# sensorCR123.net
KiCad netlist of a schematic drawn in EAGLE
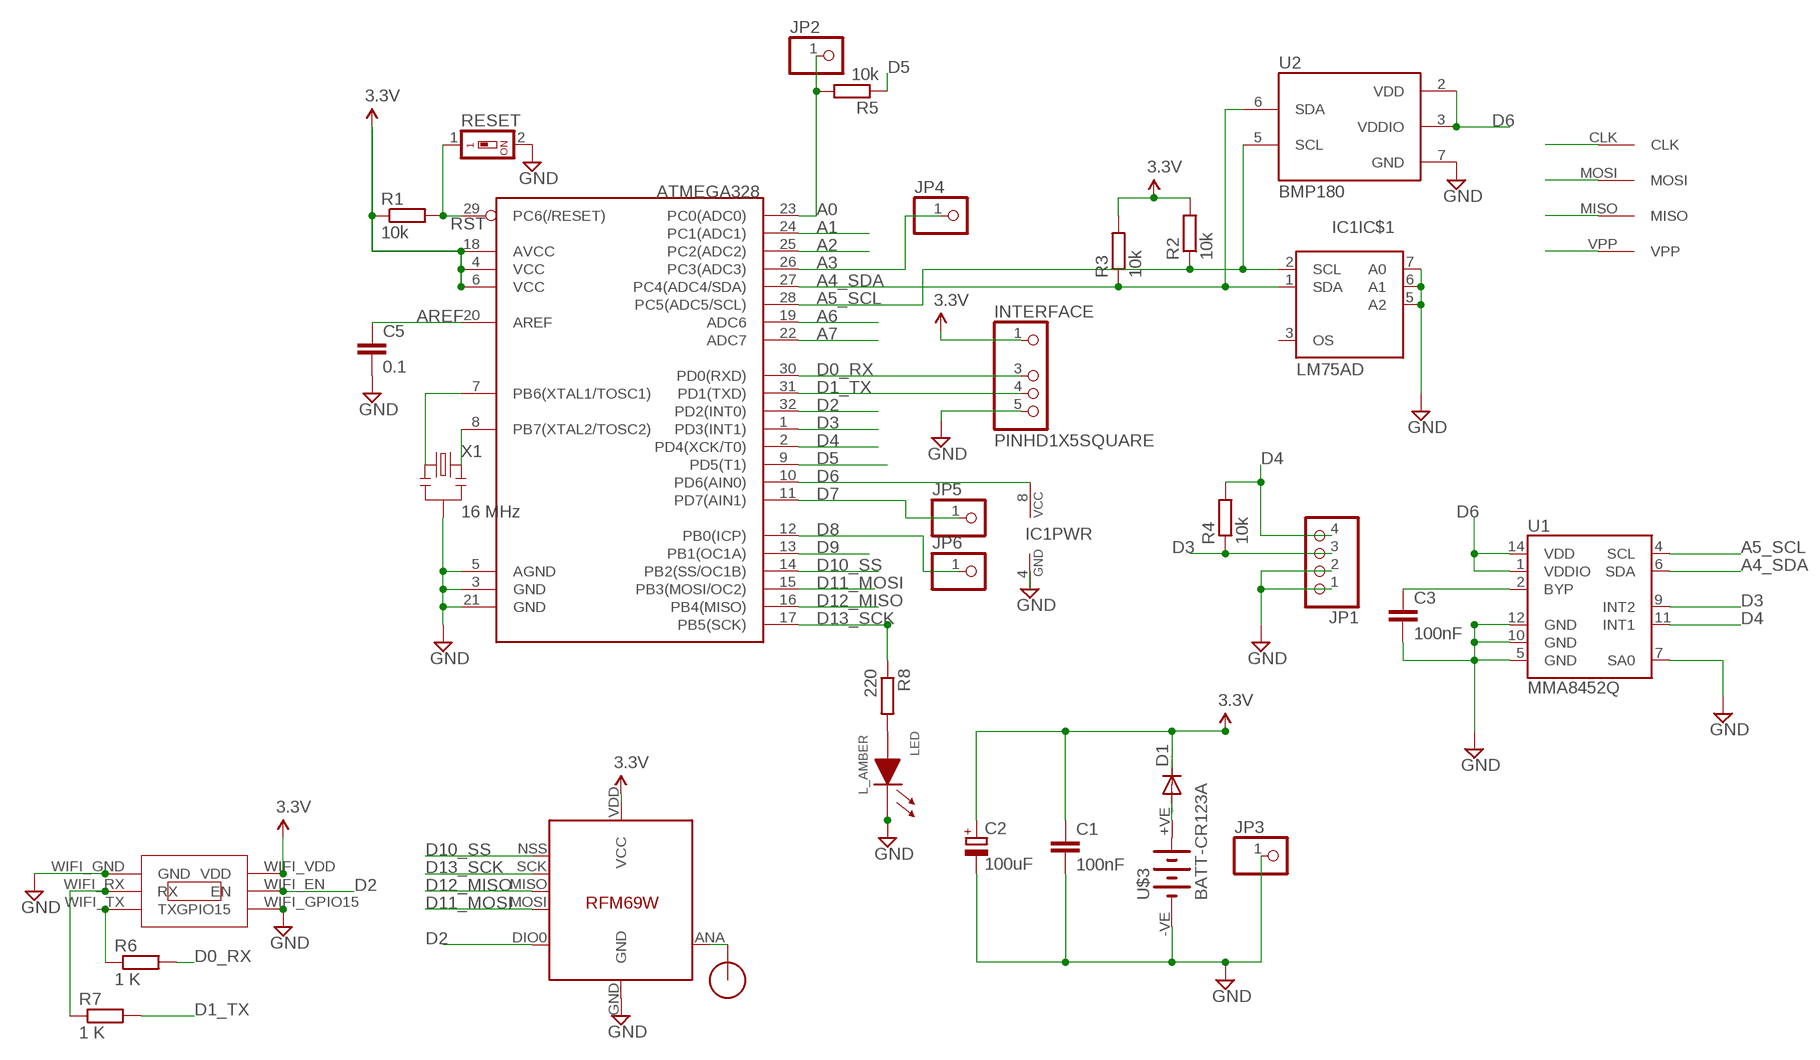
[diagram p0: schematic, sheet 1]

(export (version "E")
  (design (tool "Eeschema 10.0.6"))
  (components
    (comp (ref "ATMEGA328")
      (value "ATMega-328")
      (footprint "eagle-import:TQFP32-08")
      (libsource (lib "eagle-import") (part "ATMEGA168/328TQFP32"))
    )
    (comp (ref "C1")
      (value "100nF")
      (footprint "eagle-import:C2012")
      (libsource (lib "eagle-import") (part "C-EUC2012"))
    )
    (comp (ref "C2")
      (value "100uF")
      (footprint "eagle-import:SMC_B")
      (libsource (lib "eagle-import") (part "CPOL-EUSMCB"))
    )
    (comp (ref "C3")
      (value "100nF")
      (footprint "eagle-import:C2012")
      (libsource (lib "eagle-import") (part "C-EUC2012"))
    )
    (comp (ref "C5")
      (value "0.1")
      (footprint "eagle-import:C2012")
      (libsource (lib "eagle-import") (part "C-EUC2012"))
    )
    (comp (ref "D1")
      (value "DIODE-DO214BA")
      (footprint "eagle-import:DO214BA")
      (libsource (lib "eagle-import") (part "DIODE-DO214BA"))
    )
    (comp (ref "IC1")
      (value "LM75AD")
      (footprint "eagle-import:SO08")
      (libsource (lib "eagle-import") (part "LM75AD"))
    )
    (comp (ref "INTERFACE")
      (value "PINHD1X5SQUARE")
      (footprint "eagle-import:PINHD1X05-SQUARE")
      (libsource (lib "eagle-import") (part "PINHD1X5SQUARE"))
    )
    (comp (ref "JP1")
      (value "PINHD-1X04_2.54-S")
      (footprint "eagle-import:1X04-S")
      (libsource (lib "eagle-import") (part "PINHD-1X04_2.54-S"))
    )
    (comp (ref "JP2")
      (value "PINHD-1X01_2.54")
      (footprint "eagle-import:1X01")
      (libsource (lib "eagle-import") (part "PINHD-1X01_2.54"))
    )
    (comp (ref "JP3")
      (value "PINHD-1X01_2.54")
      (footprint "eagle-import:1X01")
      (libsource (lib "eagle-import") (part "PINHD-1X01_2.54"))
    )
    (comp (ref "JP4")
      (value "PINHD-1X01_2.54")
      (footprint "eagle-import:1X01")
      (libsource (lib "eagle-import") (part "PINHD-1X01_2.54"))
    )
    (comp (ref "JP5")
      (value "PINHD-1X01_2.54")
      (footprint "eagle-import:1X01")
      (libsource (lib "eagle-import") (part "PINHD-1X01_2.54"))
    )
    (comp (ref "JP6")
      (value "PINHD-1X01_2.54")
      (footprint "eagle-import:1X01")
      (libsource (lib "eagle-import") (part "PINHD-1X01_2.54"))
    )
    (comp (ref "LED")
      (value "L_AMBER")
      (footprint "eagle-import:LED0805")
      (libsource (lib "eagle-import") (part "LED0805"))
    )
    (comp (ref "R1")
      (value "10k")
      (footprint "eagle-import:R2012")
      (libsource (lib "eagle-import") (part "R-EU_R2012"))
    )
    (comp (ref "R2")
      (value "10k")
      (footprint "eagle-import:R2012")
      (libsource (lib "eagle-import") (part "R-EU_R2012"))
    )
    (comp (ref "R3")
      (value "10k")
      (footprint "eagle-import:R2012")
      (libsource (lib "eagle-import") (part "R-EU_R2012"))
    )
    (comp (ref "R4")
      (value "10k")
      (footprint "eagle-import:R2012")
      (libsource (lib "eagle-import") (part "R-EU_R2012"))
    )
    (comp (ref "R5")
      (value "10k")
      (footprint "eagle-import:R2012")
      (libsource (lib "eagle-import") (part "R-EU_R2012"))
    )
    (comp (ref "R6")
      (value "1 K")
      (footprint "eagle-import:M2012")
      (libsource (lib "eagle-import") (part "R-EU_M2012"))
    )
    (comp (ref "R7")
      (value "1 K")
      (footprint "eagle-import:M2012")
      (libsource (lib "eagle-import") (part "R-EU_M2012"))
    )
    (comp (ref "R8")
      (value "220")
      (footprint "eagle-import:M2012")
      (libsource (lib "eagle-import") (part "R-EU_M2012"))
    )
    (comp (ref "RESET")
      (value "SWS001")
      (footprint "eagle-import:SMS-001")
      (libsource (lib "eagle-import") (part "SWS001"))
    )
    (comp (ref "U$1")
      (value "RFM12B_ANTENNA")
      (footprint "eagle-import:RFM12B-ANTENNA")
      (libsource (lib "eagle-import") (part "RFM12B_ANTENNA"))
    )
    (comp (ref "U$2")
      (value "AVRHEADERDIP")
      (footprint "eagle-import:AVRHEADER")
      (libsource (lib "eagle-import") (part "AVRHEADERDIP"))
    )
    (comp (ref "U$3")
      (value "BATT-CR123A")
      (footprint "eagle-import:KEYSTONE-2_3A")
      (libsource (lib "eagle-import") (part "BATT-CR123A"))
    )
    (comp (ref "U$4")
      (value "RFM69W")
      (footprint "eagle-import:RFM69W")
      (libsource (lib "eagle-import") (part "RFM69W"))
    )
    (comp (ref "U$5")
      (value "ESP03")
      (footprint "eagle-import:ESP03")
      (libsource (lib "eagle-import") (part "ESP03"))
    )
    (comp (ref "U1")
      (value "MMA8452Q")
      (footprint "eagle-import:QFN-16_0.5MM")
      (libsource (lib "eagle-import") (part "MMA8452Q"))
    )
    (comp (ref "U2")
      (value "BMP180")
      (footprint "eagle-import:BMP180")
      (libsource (lib "eagle-import") (part "BMP180"))
    )
    (comp (ref "X1")
      (value "16 MHz")
      (footprint "eagle-import:RESONATOR-SMD")
      (libsource (lib "eagle-import") (part "RESONATORSMD"))
    )
  )
  (nets
    (net (code "1") (name "/A0") (class "Default")
      (node (ref "ATMEGA328") (pin "23") (pinfunction "PC0(ADC0)_23") (pintype "bidirectional"))
      (node (ref "JP2") (pin "1") (pinfunction "1_1") (pintype "passive"))
      (node (ref "R5") (pin "2") (pinfunction "2_2") (pintype "passive"))
    )
    (net (code "2") (name "/A1") (class "Default")
      (node (ref "ATMEGA328") (pin "24") (pinfunction "PC1(ADC1)_24") (pintype "bidirectional"))
    )
    (net (code "3") (name "/A2") (class "Default")
      (node (ref "ATMEGA328") (pin "25") (pinfunction "PC2(ADC2)_25") (pintype "bidirectional"))
    )
    (net (code "4") (name "/A3") (class "Default")
      (node (ref "ATMEGA328") (pin "26") (pinfunction "PC3(ADC3)_26") (pintype "bidirectional"))
      (node (ref "JP4") (pin "1") (pinfunction "1_1") (pintype "passive"))
    )
    (net (code "5") (name "/A4_SDA") (class "Default")
      (node (ref "ATMEGA328") (pin "27") (pinfunction "PC4(ADC4/SDA)_27") (pintype "bidirectional"))
      (node (ref "IC1") (pin "1") (pinfunction "SDA_1") (pintype "bidirectional"))
      (node (ref "R3") (pin "1") (pinfunction "1_1") (pintype "passive"))
      (node (ref "U1") (pin "6") (pinfunction "SDA_6") (pintype "bidirectional"))
      (node (ref "U2") (pin "6") (pinfunction "SDA_6") (pintype "bidirectional"))
    )
    (net (code "6") (name "/A5_SCL") (class "Default")
      (node (ref "ATMEGA328") (pin "28") (pinfunction "PC5(ADC5/SCL)_28") (pintype "bidirectional"))
      (node (ref "IC1") (pin "2") (pinfunction "SCL_2") (pintype "input"))
      (node (ref "R2") (pin "1") (pinfunction "1_1") (pintype "passive"))
      (node (ref "U1") (pin "4") (pinfunction "SCL_4") (pintype "bidirectional"))
      (node (ref "U2") (pin "5") (pinfunction "SCL_5") (pintype "input"))
    )
    (net (code "7") (name "/A6") (class "Default")
      (node (ref "ATMEGA328") (pin "19") (pinfunction "ADC6_19") (pintype "bidirectional"))
    )
    (net (code "8") (name "/A7") (class "Default")
      (node (ref "ATMEGA328") (pin "22") (pinfunction "ADC7_22") (pintype "bidirectional"))
    )
    (net (code "9") (name "/AREF") (class "Default")
      (node (ref "ATMEGA328") (pin "20") (pinfunction "AREF_20") (pintype "bidirectional"))
      (node (ref "C5") (pin "1") (pinfunction "1_1") (pintype "passive"))
    )
    (net (code "10") (name "/D0_RX") (class "Default")
      (node (ref "ATMEGA328") (pin "30") (pinfunction "PD0(RXD)_30") (pintype "bidirectional"))
      (node (ref "INTERFACE") (pin "3") (pinfunction "3_3") (pintype "passive"))
      (node (ref "R6") (pin "2") (pinfunction "2_2") (pintype "passive"))
    )
    (net (code "11") (name "/D1_TX") (class "Default")
      (node (ref "ATMEGA328") (pin "31") (pinfunction "PD1(TXD)_31") (pintype "bidirectional"))
      (node (ref "INTERFACE") (pin "4") (pinfunction "4_4") (pintype "passive"))
      (node (ref "R7") (pin "2") (pinfunction "2_2") (pintype "passive"))
    )
    (net (code "12") (name "/D2") (class "Default")
      (node (ref "ATMEGA328") (pin "32") (pinfunction "PD2(INT0)_32") (pintype "bidirectional"))
      (node (ref "U$4") (pin "DIO0") (pinfunction "DIO0_DIO0") (pintype "open_collector"))
      (node (ref "U$5") (pin "WIFI_EN") (pinfunction "EN_WIFI_EN") (pintype "input"))
    )
    (net (code "13") (name "/D3") (class "Default")
      (node (ref "ATMEGA328") (pin "1") (pinfunction "PD3(INT1)_1") (pintype "bidirectional"))
      (node (ref "JP1") (pin "3") (pinfunction "3_3") (pintype "passive"))
      (node (ref "R4") (pin "1") (pinfunction "1_1") (pintype "passive"))
      (node (ref "U1") (pin "9") (pinfunction "INT2_9") (pintype "bidirectional"))
    )
    (net (code "14") (name "/D4") (class "Default")
      (node (ref "ATMEGA328") (pin "2") (pinfunction "PD4(XCK/T0)_2") (pintype "bidirectional"))
      (node (ref "JP1") (pin "4") (pinfunction "4_4") (pintype "passive"))
      (node (ref "R4") (pin "2") (pinfunction "2_2") (pintype "passive"))
      (node (ref "U1") (pin "11") (pinfunction "INT1_11") (pintype "bidirectional"))
    )
    (net (code "15") (name "/D5") (class "Default")
      (node (ref "ATMEGA328") (pin "9") (pinfunction "PD5(T1)_9") (pintype "bidirectional"))
      (node (ref "R5") (pin "1") (pinfunction "1_1") (pintype "passive"))
    )
    (net (code "16") (name "/D6") (class "Default")
      (node (ref "ATMEGA328") (pin "10") (pinfunction "PD6(AIN0)_10") (pintype "bidirectional"))
      (node (ref "IC1") (pin "8") (pinfunction "VCC_8") (pintype "power_in"))
      (node (ref "U1") (pin "1") (pinfunction "VDDIO_1") (pintype "bidirectional"))
      (node (ref "U1") (pin "14") (pinfunction "VDD_14") (pintype "bidirectional"))
      (node (ref "U2") (pin "2") (pinfunction "VDD_2") (pintype "power_in"))
      (node (ref "U2") (pin "3") (pinfunction "VDDIO_3") (pintype "power_in"))
    )
    (net (code "17") (name "/D7") (class "Default")
      (node (ref "ATMEGA328") (pin "11") (pinfunction "PD7(AIN1)_11") (pintype "bidirectional"))
      (node (ref "JP5") (pin "1") (pinfunction "1_1") (pintype "passive"))
    )
    (net (code "18") (name "/D8") (class "Default")
      (node (ref "ATMEGA328") (pin "12") (pinfunction "PB0(ICP)_12") (pintype "bidirectional"))
      (node (ref "JP6") (pin "1") (pinfunction "1_1") (pintype "passive"))
    )
    (net (code "19") (name "/D9") (class "Default")
      (node (ref "ATMEGA328") (pin "13") (pinfunction "PB1(OC1A)_13") (pintype "bidirectional"))
    )
    (net (code "20") (name "/D10_SS") (class "Default")
      (node (ref "ATMEGA328") (pin "14") (pinfunction "PB2(SS/OC1B)_14") (pintype "bidirectional"))
      (node (ref "U$4") (pin "NSS") (pinfunction "SEL_NSS") (pintype "input"))
    )
    (net (code "21") (name "/D11_MOSI") (class "Default")
      (node (ref "ATMEGA328") (pin "15") (pinfunction "PB3(MOSI/OC2)_15") (pintype "bidirectional"))
      (node (ref "U$2") (pin "MOSI") (pinfunction "MOSI_MOSI") (pintype "bidirectional"))
      (node (ref "U$4") (pin "MOSI") (pinfunction "MOSI_MOSI") (pintype "output"))
    )
    (net (code "22") (name "/D12_MISO") (class "Default")
      (node (ref "ATMEGA328") (pin "16") (pinfunction "PB4(MISO)_16") (pintype "bidirectional"))
      (node (ref "U$2") (pin "MISO") (pinfunction "MISO_MISO") (pintype "bidirectional"))
      (node (ref "U$4") (pin "MISO") (pinfunction "MISO_MISO") (pintype "input"))
    )
    (net (code "23") (name "/D13_SCK") (class "Default")
      (node (ref "ATMEGA328") (pin "17") (pinfunction "PB5(SCK)_17") (pintype "bidirectional"))
      (node (ref "R8") (pin "1") (pinfunction "1_1") (pintype "passive"))
      (node (ref "U$2") (pin "CLK") (pinfunction "CLK_CLK") (pintype "bidirectional"))
      (node (ref "U$4") (pin "SCK") (pinfunction "SCK_SCK") (pintype "input"))
    )
    (net (code "24") (name "/RST") (class "Default")
      (node (ref "ATMEGA328") (pin "29") (pinfunction "PC6(/RESET)_29") (pintype "bidirectional"))
      (node (ref "R1") (pin "2") (pinfunction "2_2") (pintype "passive"))
      (node (ref "RESET") (pin "1") (pinfunction "1_1") (pintype "passive"))
      (node (ref "U$2") (pin "VPP") (pinfunction "VPP_VPP") (pintype "bidirectional"))
    )
    (net (code "25") (name "3.3V") (class "Default")
      (node (ref "ATMEGA328") (pin "18") (pinfunction "AVCC_18") (pintype "bidirectional"))
      (node (ref "ATMEGA328") (pin "4") (pinfunction "VCC_4") (pintype "bidirectional"))
      (node (ref "ATMEGA328") (pin "6") (pinfunction "VCC_6") (pintype "bidirectional"))
      (node (ref "C1") (pin "1") (pinfunction "1_1") (pintype "passive"))
      (node (ref "C2") (pin "+") (pinfunction "+_+") (pintype "passive"))
      (node (ref "D1") (pin "C") (pinfunction "C_C") (pintype "passive"))
      (node (ref "INTERFACE") (pin "1") (pinfunction "1_1") (pintype "passive"))
      (node (ref "R1") (pin "1") (pinfunction "1_1") (pintype "passive"))
      (node (ref "R2") (pin "2") (pinfunction "2_2") (pintype "passive"))
      (node (ref "R3") (pin "2") (pinfunction "2_2") (pintype "passive"))
      (node (ref "U$4") (pin "VDD") (pinfunction "VCC_VDD") (pintype "power_in"))
      (node (ref "U$5") (pin "WIFI_VDD") (pinfunction "VDD_WIFI_VDD") (pintype "power_in"))
    )
    (net (code "26") (name "GND") (class "Default")
      (node (ref "ATMEGA328") (pin "21") (pinfunction "GND_21") (pintype "bidirectional"))
      (node (ref "ATMEGA328") (pin "3") (pinfunction "GND_3") (pintype "bidirectional"))
      (node (ref "ATMEGA328") (pin "5") (pinfunction "AGND_5") (pintype "bidirectional"))
      (node (ref "C1") (pin "2") (pinfunction "2_2") (pintype "passive"))
      (node (ref "C2") (pin "-") (pinfunction "-_-") (pintype "passive"))
      (node (ref "C3") (pin "2") (pinfunction "2_2") (pintype "passive"))
      (node (ref "C5") (pin "2") (pinfunction "2_2") (pintype "passive"))
      (node (ref "IC1") (pin "4") (pinfunction "GND_4") (pintype "power_in"))
      (node (ref "IC1") (pin "5") (pinfunction "A2_5") (pintype "input"))
      (node (ref "IC1") (pin "6") (pinfunction "A1_6") (pintype "input"))
      (node (ref "IC1") (pin "7") (pinfunction "A0_7") (pintype "input"))
      (node (ref "INTERFACE") (pin "5") (pinfunction "5_5") (pintype "passive"))
      (node (ref "JP1") (pin "1") (pinfunction "1_1") (pintype "passive"))
      (node (ref "JP1") (pin "2") (pinfunction "2_2") (pintype "passive"))
      (node (ref "JP3") (pin "1") (pinfunction "1_1") (pintype "passive"))
      (node (ref "LED") (pin "1") (pinfunction "CA_1") (pintype "passive"))
      (node (ref "RESET") (pin "2") (pinfunction "2_2") (pintype "passive"))
      (node (ref "U$3") (pin "-VE") (pinfunction "-_-VE") (pintype "passive"))
      (node (ref "U$4") (pin "GND") (pinfunction "GND_GND") (pintype "power_in"))
      (node (ref "U$5") (pin "WIFI_GND") (pinfunction "GND_WIFI_GND") (pintype "power_in"))
      (node (ref "U$5") (pin "WIFI_GPIO15") (pinfunction "GPIO15_WIFI_GPIO15") (pintype "input"))
      (node (ref "U1") (pin "10") (pinfunction "GND_10") (pintype "bidirectional"))
      (node (ref "U1") (pin "12") (pinfunction "GND_12") (pintype "bidirectional"))
      (node (ref "U1") (pin "5") (pinfunction "GND_5") (pintype "bidirectional"))
      (node (ref "U1") (pin "7") (pinfunction "SA0_7") (pintype "bidirectional"))
      (node (ref "U2") (pin "7") (pinfunction "GND_7") (pintype "power_in"))
      (node (ref "X1") (pin "2") (pinfunction "2_2") (pintype "passive"))
    )
    (net (code "27") (name "Net-(ATMEGA328-PB6(XTAL1{slash}TOSC1))") (class "Default")
      (node (ref "ATMEGA328") (pin "7") (pinfunction "PB6(XTAL1/TOSC1)_7") (pintype "bidirectional"))
      (node (ref "X1") (pin "1") (pinfunction "1_1") (pintype "passive"))
    )
    (net (code "28") (name "Net-(ATMEGA328-PB7(XTAL2{slash}TOSC2))") (class "Default")
      (node (ref "ATMEGA328") (pin "8") (pinfunction "PB7(XTAL2/TOSC2)_8") (pintype "bidirectional"))
      (node (ref "X1") (pin "3") (pinfunction "3_3") (pintype "passive"))
    )
    (net (code "29") (name "Net-(LED-AN)") (class "Default")
      (node (ref "LED") (pin "2") (pinfunction "AN_2") (pintype "passive"))
      (node (ref "R8") (pin "2") (pinfunction "2_2") (pintype "passive"))
    )
    (net (code "30") (name "Net-(U$1-1)") (class "Default")
      (node (ref "U$1") (pin "P$1") (pinfunction "1_P$1") (pintype "bidirectional"))
      (node (ref "U$4") (pin "ANA") (pinfunction "ANT_ANA") (pintype "passive"))
    )
    (net (code "31") (name "Net-(U$3-+)") (class "Default")
      (node (ref "D1") (pin "A") (pinfunction "A_A") (pintype "passive"))
      (node (ref "U$3") (pin "+VE") (pinfunction "+_+VE") (pintype "passive"))
    )
    (net (code "32") (name "Net-(U$5-RX)") (class "Default")
      (node (ref "R7") (pin "1") (pinfunction "1_1") (pintype "passive"))
      (node (ref "U$5") (pin "WIFI_RX") (pinfunction "RX_WIFI_RX") (pintype "input"))
    )
    (net (code "33") (name "Net-(U$5-TX)") (class "Default")
      (node (ref "R6") (pin "1") (pinfunction "1_1") (pintype "passive"))
      (node (ref "U$5") (pin "WIFI_TX") (pinfunction "TX_WIFI_TX") (pintype "output"))
    )
    (net (code "34") (name "Net-(U1-BYP)") (class "Default")
      (node (ref "C3") (pin "1") (pinfunction "1_1") (pintype "passive"))
      (node (ref "U1") (pin "2") (pinfunction "BYP_2") (pintype "bidirectional"))
    )
    (net (code "35") (name "unconnected-(IC1A-OS-Pad3)") (class "Default")
      (node (ref "IC1") (pin "3") (pinfunction "OS_3") (pintype "output"))
    )
  )
)
